# Sheet1.net
KiCad netlist of a schematic drawn in Altium Designer
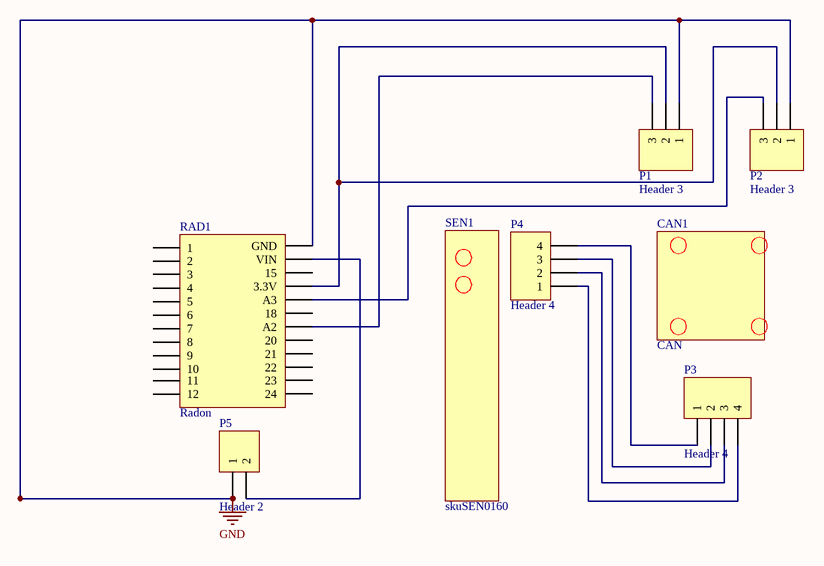
[diagram p0: Sheet1.SchDoc]

(export (version "E")
  (design (tool "Eeschema 10.0.6"))
  (components
    (comp (ref "CAN1")
      (value "CAN")
      (footprint "CAN")
      (description "CAN for weight sensor skuSEN0160")
      (libsource (lib "Schlib2") (part "CAN"))
    )
    (comp (ref "P1")
      (value "Header 3")
      (footprint "HDR1X3")
      (description "Header, 3-Pin")
      (fields (field (name "PUBLISHER") "Altium Limited"))
      (libsource (lib "Miscellaneous Connectors") (part "Header 3"))
    )
    (comp (ref "P2")
      (value "Header 3")
      (footprint "HDR1X3")
      (description "Header, 3-Pin")
      (fields (field (name "PUBLISHER") "Altium Limited"))
      (libsource (lib "Miscellaneous Connectors") (part "Header 3"))
    )
    (comp (ref "P3")
      (value "Header 4")
      (footprint "HDR1X4")
      (description "Header, 4-Pin")
      (fields (field (name "PUBLISHER") "Altium Limited"))
      (libsource (lib "") (part "Header 4_1"))
    )
    (comp (ref "P4")
      (value "Header 4")
      (footprint "HDR1X4")
      (description "Header, 4-Pin")
      (fields (field (name "PUBLISHER") "Altium Limited"))
      (libsource (lib "Miscellaneous Connectors") (part "Header 4"))
    )
    (comp (ref "P5")
      (value "Header 2")
      (footprint "HDR1X2")
      (description "Header, 2-Pin")
      (fields (field (name "PUBLISHER") "Altium Limited"))
      (libsource (lib "Miscellaneous Connectors") (part "Header 2"))
    )
    (comp (ref "RAD1")
      (value "Radon")
      (footprint "radon")
      (description "Arduino Radon")
      (fields (field (name "PUBLISHER") "Altium Limited"))
      (libsource (lib "Schlib1") (part "Radon"))
    )
    (comp (ref "SEN1")
      (value "skuSEN0160")
      (footprint "skuSEN0160")
      (description "weight sensor skuSEN0160")
      (libsource (lib "Schlib3") (part "skuSEN0160"))
    )
  )
  (nets
    (net (code "1") (name "GND") (class "Default")
      (node (ref "P1") (pin "1") (pinfunction "1_1") (pintype "passive"))
      (node (ref "P2") (pin "1") (pinfunction "1_1") (pintype "passive"))
      (node (ref "P5") (pin "1") (pinfunction "1_1") (pintype "passive"))
      (node (ref "RAD1") (pin "13") (pinfunction "GND_13") (pintype "passive"))
    )
    (net (code "2") (name "Net-(P3-Pad1)") (class "Default")
      (node (ref "P3") (pin "1") (pinfunction "1_1") (pintype "passive"))
      (node (ref "P4") (pin "4") (pinfunction "4_4") (pintype "passive"))
    )
    (net (code "3") (name "Net-(P3-Pad2)") (class "Default")
      (node (ref "P3") (pin "2") (pinfunction "2_2") (pintype "passive"))
      (node (ref "P4") (pin "3") (pinfunction "3_3") (pintype "passive"))
    )
    (net (code "4") (name "Net-(P3-Pad3)") (class "Default")
      (node (ref "P3") (pin "3") (pinfunction "3_3") (pintype "passive"))
      (node (ref "P4") (pin "2") (pinfunction "2_2") (pintype "passive"))
    )
    (net (code "5") (name "Net-(P3-Pad4)") (class "Default")
      (node (ref "P3") (pin "4") (pinfunction "4_4") (pintype "passive"))
      (node (ref "P4") (pin "1") (pinfunction "1_1") (pintype "passive"))
    )
    (net (code "6") (name "Net-(RAD1-3.3V)") (class "Default")
      (node (ref "P1") (pin "2") (pinfunction "2_2") (pintype "passive"))
      (node (ref "P2") (pin "2") (pinfunction "2_2") (pintype "passive"))
      (node (ref "RAD1") (pin "16") (pinfunction "3.3V_16") (pintype "passive"))
    )
    (net (code "7") (name "Net-(RAD1-A2)") (class "Default")
      (node (ref "P1") (pin "3") (pinfunction "3_3") (pintype "passive"))
      (node (ref "RAD1") (pin "19") (pinfunction "A2_19") (pintype "passive"))
    )
    (net (code "8") (name "Net-(RAD1-A3)") (class "Default")
      (node (ref "P2") (pin "3") (pinfunction "3_3") (pintype "passive"))
      (node (ref "RAD1") (pin "17") (pinfunction "A3_17") (pintype "passive"))
    )
    (net (code "9") (name "Net-(RAD1-VIN)") (class "Default")
      (node (ref "P5") (pin "2") (pinfunction "2_2") (pintype "passive"))
      (node (ref "RAD1") (pin "14") (pinfunction "VIN_14") (pintype "passive"))
    )
    (net (code "10") (name "unconnected-(RAD1-Pad1)") (class "Default")
      (node (ref "RAD1") (pin "1") (pinfunction "1_1") (pintype "passive"))
    )
    (net (code "11") (name "unconnected-(RAD1-Pad2)") (class "Default")
      (node (ref "RAD1") (pin "2") (pinfunction "2_2") (pintype "passive"))
    )
    (net (code "12") (name "unconnected-(RAD1-Pad3)") (class "Default")
      (node (ref "RAD1") (pin "3") (pinfunction "3_3") (pintype "passive"))
    )
    (net (code "13") (name "unconnected-(RAD1-Pad4)") (class "Default")
      (node (ref "RAD1") (pin "4") (pinfunction "4_4") (pintype "passive"))
    )
    (net (code "14") (name "unconnected-(RAD1-Pad5)") (class "Default")
      (node (ref "RAD1") (pin "5") (pinfunction "5_5") (pintype "passive"))
    )
    (net (code "15") (name "unconnected-(RAD1-Pad6)") (class "Default")
      (node (ref "RAD1") (pin "6") (pinfunction "6_6") (pintype "passive"))
    )
    (net (code "16") (name "unconnected-(RAD1-Pad7)") (class "Default")
      (node (ref "RAD1") (pin "7") (pinfunction "7_7") (pintype "passive"))
    )
    (net (code "17") (name "unconnected-(RAD1-Pad8)") (class "Default")
      (node (ref "RAD1") (pin "8") (pinfunction "8_8") (pintype "passive"))
    )
    (net (code "18") (name "unconnected-(RAD1-Pad9)") (class "Default")
      (node (ref "RAD1") (pin "9") (pinfunction "9_9") (pintype "passive"))
    )
    (net (code "19") (name "unconnected-(RAD1-Pad10)") (class "Default")
      (node (ref "RAD1") (pin "10") (pinfunction "10_10") (pintype "passive"))
    )
    (net (code "20") (name "unconnected-(RAD1-Pad11)") (class "Default")
      (node (ref "RAD1") (pin "11") (pinfunction "11_11") (pintype "passive"))
    )
    (net (code "21") (name "unconnected-(RAD1-Pad12)") (class "Default")
      (node (ref "RAD1") (pin "12") (pinfunction "12_12") (pintype "passive"))
    )
    (net (code "22") (name "unconnected-(RAD1-Pad15)") (class "Default")
      (node (ref "RAD1") (pin "15") (pinfunction "15_15") (pintype "passive"))
    )
    (net (code "23") (name "unconnected-(RAD1-Pad18)") (class "Default")
      (node (ref "RAD1") (pin "18") (pinfunction "18_18") (pintype "passive"))
    )
    (net (code "24") (name "unconnected-(RAD1-Pad20)") (class "Default")
      (node (ref "RAD1") (pin "20") (pinfunction "20_20") (pintype "passive"))
    )
    (net (code "25") (name "unconnected-(RAD1-Pad21)") (class "Default")
      (node (ref "RAD1") (pin "21") (pinfunction "21_21") (pintype "passive"))
    )
    (net (code "26") (name "unconnected-(RAD1-Pad22)") (class "Default")
      (node (ref "RAD1") (pin "22") (pinfunction "22_22") (pintype "passive"))
    )
    (net (code "27") (name "unconnected-(RAD1-Pad23)") (class "Default")
      (node (ref "RAD1") (pin "23") (pinfunction "23_23") (pintype "passive"))
    )
    (net (code "28") (name "unconnected-(RAD1-Pad24)") (class "Default")
      (node (ref "RAD1") (pin "24") (pinfunction "24_24") (pintype "passive"))
    )
  )
)
